# mugsyBrainBoard_p08.net
KiCad netlist of a schematic drawn in EAGLE
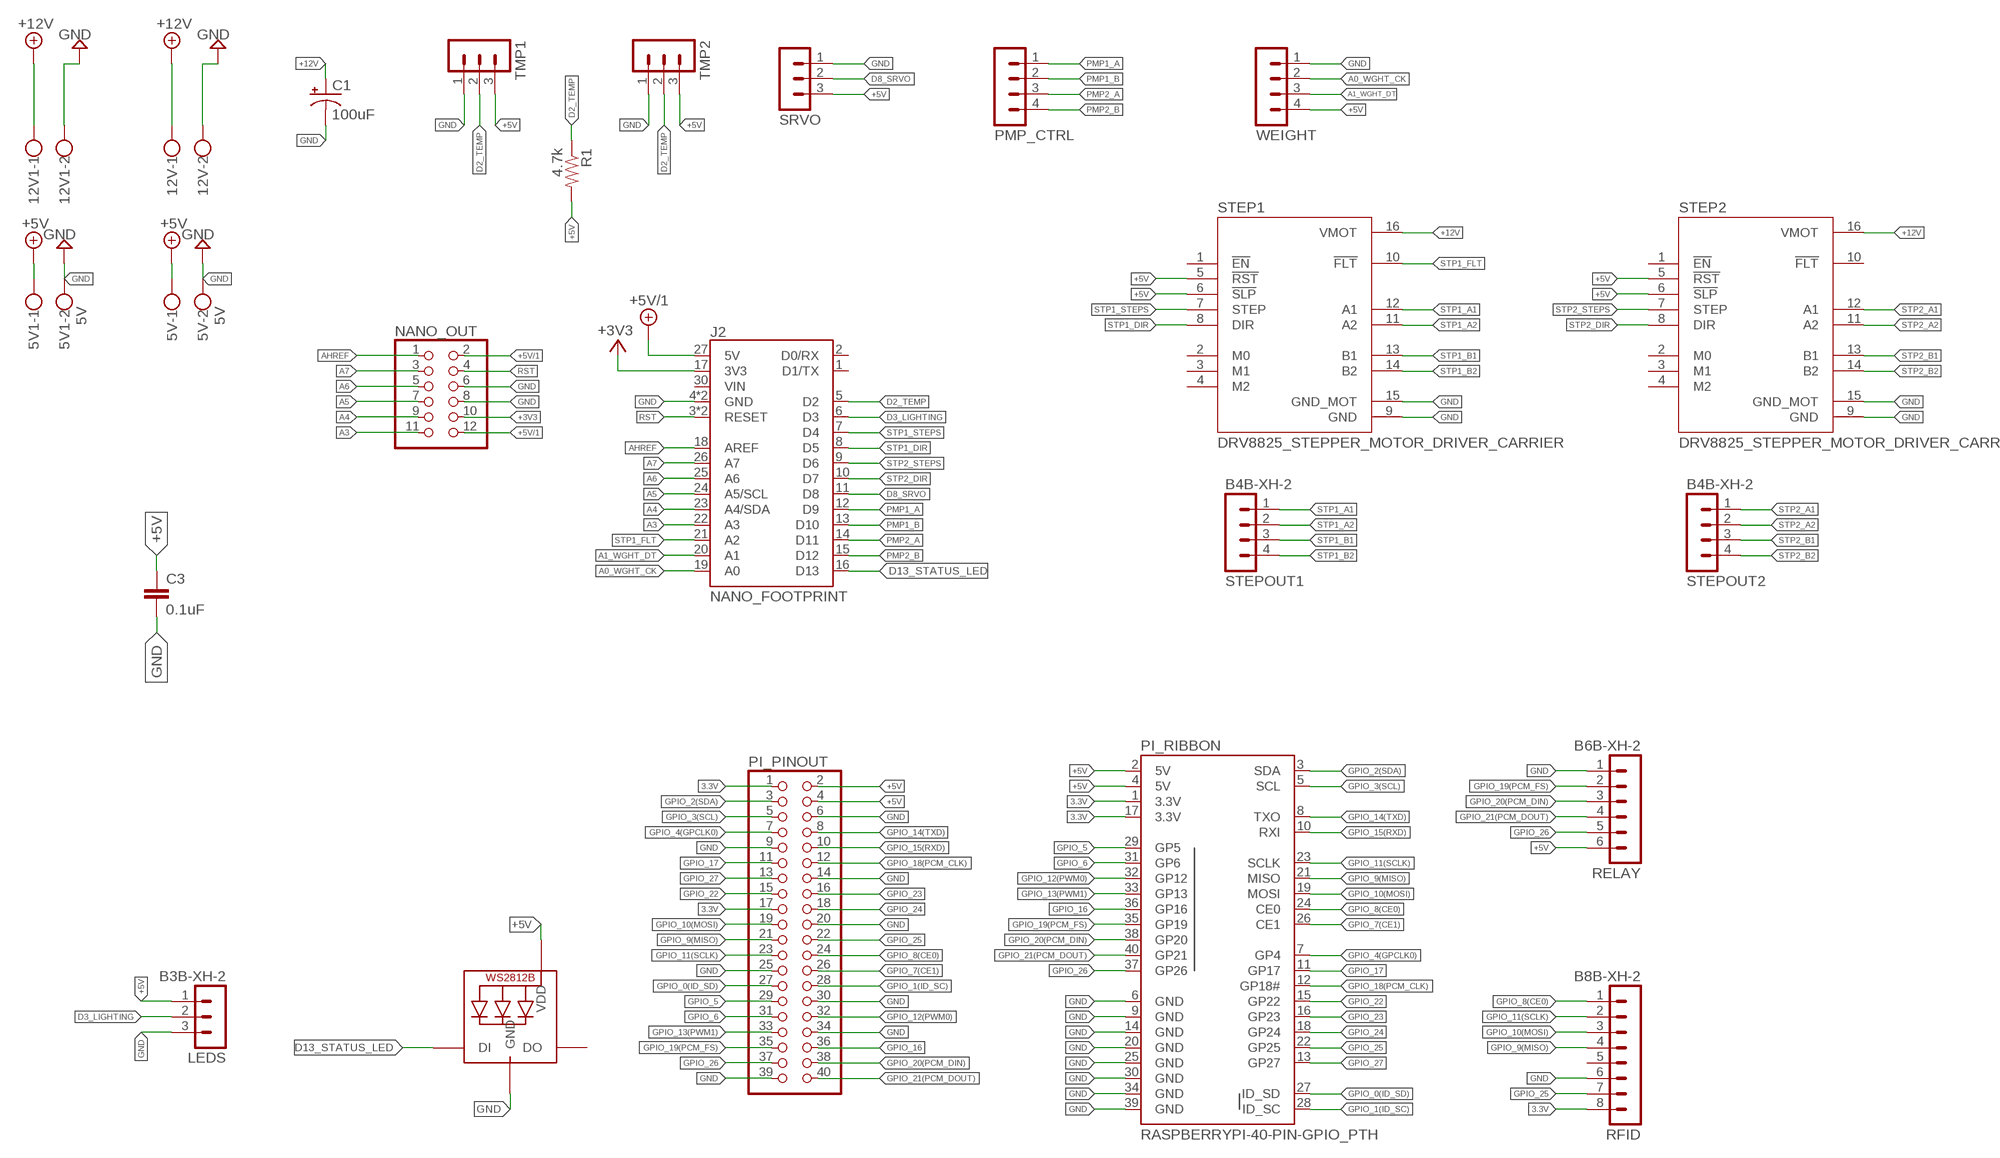
[diagram p0: schematic, sheet 1]

(export (version "E")
  (design (tool "Eeschema 10.0.6"))
  (components
    (comp (ref "5V")
      (value "5V")
      (footprint "eagle-import:W237-102")
      (fields (field (name "MPN") "237-102"))
      (libsource (lib "eagle-import") (part "W237-102"))
    )
    (comp (ref "5V1")
      (value "5V")
      (footprint "eagle-import:W237-102")
      (fields (field (name "MPN") "237-102"))
      (libsource (lib "eagle-import") (part "W237-102"))
    )
    (comp (ref "12V")
      (value "W237-102")
      (footprint "eagle-import:W237-102")
      (fields (field (name "MPN") "237-102"))
      (libsource (lib "eagle-import") (part "W237-102"))
    )
    (comp (ref "12V1")
      (value "W237-102")
      (footprint "eagle-import:W237-102")
      (fields (field (name "MPN") "237-102"))
      (libsource (lib "eagle-import") (part "W237-102"))
    )
    (comp (ref "C1")
      (value "100uF")
      (footprint "eagle-import:CPOL-RADIAL-2.5MM-6.5MM")
      (libsource (lib "eagle-import") (part "100UF-POLAR-RADIAL-2.5MM-25V-20%"))
    )
    (comp (ref "C3")
      (value "0.1uF")
      (footprint "eagle-import:C050-030X075")
      (libsource (lib "eagle-import") (part "C-EU050-030X075"))
    )
    (comp (ref "J2")
      (value "NANO_FOOTPRINT")
      (footprint "eagle-import:NANO")
      (libsource (lib "eagle-import") (part "NANO_FOOTPRINT"))
    )
    (comp (ref "LEDS")
      (value "B3B-XH-2")
      (footprint "eagle-import:B3B-XH-A")
      (libsource (lib "eagle-import") (part "B3B-XH-2"))
    )
    (comp (ref "NANO_OUT")
      (value "PINHD-2X6")
      (footprint "eagle-import:2X06")
      (libsource (lib "eagle-import") (part "PINHD-2X6"))
    )
    (comp (ref "PI_PINOUT")
      (value "PINHD-2X20")
      (footprint "eagle-import:2X20")
      (libsource (lib "eagle-import") (part "PINHD-2X20"))
    )
    (comp (ref "PI_RIBBON")
      (value "RASPBERRYPI-40-PIN-GPIO_PTH")
      (footprint "eagle-import:2X20_SHROUDED")
      (libsource (lib "eagle-import") (part "RASPBERRYPI-40-PIN-GPIO_PTH"))
    )
    (comp (ref "PMP_CTRL")
      (value "B4B-XH-2")
      (footprint "eagle-import:B4B-XH-A")
      (libsource (lib "eagle-import") (part "B4B-XH-2"))
    )
    (comp (ref "R1")
      (value "4.7k")
      (footprint "eagle-import:0207_5V")
      (libsource (lib "eagle-import") (part "R-US_0207/5V"))
    )
    (comp (ref "RELAY")
      (value "B6B-XH-2")
      (footprint "eagle-import:B6B-XH-A")
      (libsource (lib "eagle-import") (part "B6B-XH-2"))
    )
    (comp (ref "RFID")
      (value "B8B-XH-2")
      (footprint "eagle-import:B8B-XH-A")
      (libsource (lib "eagle-import") (part "B8B-XH-2"))
    )
    (comp (ref "SRVO")
      (value "B3B-XH-2")
      (footprint "eagle-import:B3B-XH-A")
      (libsource (lib "eagle-import") (part "B3B-XH-2"))
    )
    (comp (ref "STATUS")
      (value "WS2812B5050")
      (footprint "eagle-import:WS2812B")
      (libsource (lib "eagle-import") (part "WS2812B5050"))
    )
    (comp (ref "STEP1")
      (value "DRV8825_STEPPER_MOTOR_DRIVER_CARRIER")
      (footprint "eagle-import:IC_DRV8825_STEPPER_MOTOR_DRIVER_CARRIER")
      (fields (field (name "MF") "Pololu") (field (name "MP") "DRV8825 STEPPER MOTOR DRIVER CARRIER"))
      (libsource (lib "eagle-import") (part "DRV8825_STEPPER_MOTOR_DRIVER_CARRIER"))
    )
    (comp (ref "STEP2")
      (value "DRV8825_STEPPER_MOTOR_DRIVER_CARRIER")
      (footprint "eagle-import:IC_DRV8825_STEPPER_MOTOR_DRIVER_CARRIER")
      (fields (field (name "MF") "Pololu") (field (name "MP") "DRV8825 STEPPER MOTOR DRIVER CARRIER"))
      (libsource (lib "eagle-import") (part "DRV8825_STEPPER_MOTOR_DRIVER_CARRIER"))
    )
    (comp (ref "STEPOUT1")
      (value "B4B-XH-2")
      (footprint "eagle-import:B4B-XH-A")
      (libsource (lib "eagle-import") (part "B4B-XH-2"))
    )
    (comp (ref "STEPOUT2")
      (value "B4B-XH-2")
      (footprint "eagle-import:B4B-XH-A")
      (libsource (lib "eagle-import") (part "B4B-XH-2"))
    )
    (comp (ref "TMP1")
      (value "B3B-XH-2")
      (footprint "eagle-import:B3B-XH-A")
      (libsource (lib "eagle-import") (part "B3B-XH-2"))
    )
    (comp (ref "TMP2")
      (value "B3B-XH-2")
      (footprint "eagle-import:B3B-XH-A")
      (libsource (lib "eagle-import") (part "B3B-XH-2"))
    )
    (comp (ref "WEIGHT")
      (value "B4B-XH-2")
      (footprint "eagle-import:B4B-XH-A")
      (libsource (lib "eagle-import") (part "B4B-XH-2"))
    )
  )
  (nets
    (net (code "1") (name "+3V3") (class "Default")
      (node (ref "J2") (pin "17") (pinfunction "3V3_17") (pintype "bidirectional"))
      (node (ref "NANO_OUT") (pin "10") (pinfunction "10_10") (pintype "passive"))
    )
    (net (code "2") (name "+5V") (class "Default")
      (node (ref "5V") (pin "1") (pinfunction "KL_1") (pintype "passive"))
      (node (ref "5V1") (pin "1") (pinfunction "KL_1") (pintype "passive"))
      (node (ref "C3") (pin "1") (pinfunction "1_1") (pintype "passive"))
      (node (ref "LEDS") (pin "1") (pinfunction "1_1") (pintype "passive"))
      (node (ref "PI_PINOUT") (pin "2") (pinfunction "2_2") (pintype "passive"))
      (node (ref "PI_PINOUT") (pin "4") (pinfunction "4_4") (pintype "passive"))
      (node (ref "PI_RIBBON") (pin "2") (pinfunction "5V_2") (pintype "power_in"))
      (node (ref "PI_RIBBON") (pin "4") (pinfunction "5V_4") (pintype "power_in"))
      (node (ref "R1") (pin "2") (pinfunction "2_2") (pintype "passive"))
      (node (ref "RELAY") (pin "6") (pinfunction "6_6") (pintype "passive"))
      (node (ref "SRVO") (pin "3") (pinfunction "3_3") (pintype "passive"))
      (node (ref "STATUS") (pin "1-VDD") (pinfunction "VDD_1-VDD") (pintype "power_in"))
      (node (ref "STEP1") (pin "5") (pinfunction "~{RST}_5") (pintype "input"))
      (node (ref "STEP1") (pin "6") (pinfunction "~{SLP}_6") (pintype "input"))
      (node (ref "STEP2") (pin "5") (pinfunction "~{RST}_5") (pintype "input"))
      (node (ref "STEP2") (pin "6") (pinfunction "~{SLP}_6") (pintype "input"))
      (node (ref "TMP1") (pin "3") (pinfunction "3_3") (pintype "passive"))
      (node (ref "TMP2") (pin "3") (pinfunction "3_3") (pintype "passive"))
      (node (ref "WEIGHT") (pin "4") (pinfunction "4_4") (pintype "passive"))
    )
    (net (code "3") (name "+5V{slash}1") (class "Default")
      (node (ref "J2") (pin "27") (pinfunction "5V_27") (pintype "bidirectional"))
      (node (ref "NANO_OUT") (pin "12") (pinfunction "12_12") (pintype "passive"))
      (node (ref "NANO_OUT") (pin "2") (pinfunction "2_2") (pintype "passive"))
    )
    (net (code "4") (name "+12V") (class "Default")
      (node (ref "12V") (pin "1") (pinfunction "KL_1") (pintype "passive"))
      (node (ref "12V1") (pin "1") (pinfunction "KL_1") (pintype "passive"))
      (node (ref "C1") (pin "1") (pinfunction "+_1") (pintype "passive"))
      (node (ref "STEP1") (pin "16") (pinfunction "VMOT_16") (pintype "power_in"))
      (node (ref "STEP2") (pin "16") (pinfunction "VMOT_16") (pintype "power_in"))
    )
    (net (code "5") (name "3.3V") (class "Default")
      (node (ref "PI_PINOUT") (pin "1") (pinfunction "1_1") (pintype "passive"))
      (node (ref "PI_PINOUT") (pin "17") (pinfunction "17_17") (pintype "passive"))
      (node (ref "PI_RIBBON") (pin "1") (pinfunction "3.3V_1") (pintype "power_in"))
      (node (ref "PI_RIBBON") (pin "17") (pinfunction "3.3V_17") (pintype "power_in"))
      (node (ref "RFID") (pin "8") (pinfunction "8_8") (pintype "passive"))
    )
    (net (code "6") (name "A0_WGHT_CK") (class "Default")
      (node (ref "J2") (pin "19") (pinfunction "A0_19") (pintype "bidirectional"))
      (node (ref "WEIGHT") (pin "2") (pinfunction "2_2") (pintype "passive"))
    )
    (net (code "7") (name "A1_WGHT_DT") (class "Default")
      (node (ref "J2") (pin "20") (pinfunction "A1_20") (pintype "bidirectional"))
      (node (ref "WEIGHT") (pin "3") (pinfunction "3_3") (pintype "passive"))
    )
    (net (code "8") (name "A3") (class "Default")
      (node (ref "J2") (pin "22") (pinfunction "A3_22") (pintype "bidirectional"))
      (node (ref "NANO_OUT") (pin "11") (pinfunction "11_11") (pintype "passive"))
    )
    (net (code "9") (name "A4") (class "Default")
      (node (ref "J2") (pin "23") (pinfunction "A4/SDA_23") (pintype "bidirectional"))
      (node (ref "NANO_OUT") (pin "9") (pinfunction "9_9") (pintype "passive"))
    )
    (net (code "10") (name "A5") (class "Default")
      (node (ref "J2") (pin "24") (pinfunction "A5/SCL_24") (pintype "bidirectional"))
      (node (ref "NANO_OUT") (pin "7") (pinfunction "7_7") (pintype "passive"))
    )
    (net (code "11") (name "A6") (class "Default")
      (node (ref "J2") (pin "25") (pinfunction "A6_25") (pintype "bidirectional"))
      (node (ref "NANO_OUT") (pin "5") (pinfunction "5_5") (pintype "passive"))
    )
    (net (code "12") (name "A7") (class "Default")
      (node (ref "J2") (pin "26") (pinfunction "A7_26") (pintype "bidirectional"))
      (node (ref "NANO_OUT") (pin "3") (pinfunction "3_3") (pintype "passive"))
    )
    (net (code "13") (name "AHREF") (class "Default")
      (node (ref "J2") (pin "18") (pinfunction "AREF_18") (pintype "bidirectional"))
      (node (ref "NANO_OUT") (pin "1") (pinfunction "1_1") (pintype "passive"))
    )
    (net (code "14") (name "D2_TEMP") (class "Default")
      (node (ref "J2") (pin "5") (pinfunction "D2_5") (pintype "bidirectional"))
      (node (ref "R1") (pin "1") (pinfunction "1_1") (pintype "passive"))
      (node (ref "TMP1") (pin "2") (pinfunction "2_2") (pintype "passive"))
      (node (ref "TMP2") (pin "2") (pinfunction "2_2") (pintype "passive"))
    )
    (net (code "15") (name "D3_LIGHTING") (class "Default")
      (node (ref "J2") (pin "6") (pinfunction "D3_6") (pintype "bidirectional"))
      (node (ref "LEDS") (pin "2") (pinfunction "2_2") (pintype "passive"))
    )
    (net (code "16") (name "D8_SRVO") (class "Default")
      (node (ref "J2") (pin "11") (pinfunction "D8_11") (pintype "bidirectional"))
      (node (ref "SRVO") (pin "2") (pinfunction "2_2") (pintype "passive"))
    )
    (net (code "17") (name "D13_STATUS_LED") (class "Default")
      (node (ref "J2") (pin "16") (pinfunction "D13_16") (pintype "bidirectional"))
      (node (ref "STATUS") (pin "4-DIN") (pinfunction "DI_4-DIN") (pintype "input"))
    )
    (net (code "18") (name "GND") (class "Default")
      (node (ref "12V") (pin "2") (pinfunction "KL_2") (pintype "passive"))
      (node (ref "12V1") (pin "2") (pinfunction "KL_2") (pintype "passive"))
      (node (ref "5V") (pin "2") (pinfunction "KL_2") (pintype "passive"))
      (node (ref "5V1") (pin "2") (pinfunction "KL_2") (pintype "passive"))
      (node (ref "C1") (pin "2") (pinfunction "-_2") (pintype "passive"))
      (node (ref "C3") (pin "2") (pinfunction "2_2") (pintype "passive"))
      (node (ref "J2") (pin "29") (pinfunction "GND_29") (pintype "bidirectional"))
      (node (ref "J2") (pin "4") (pinfunction "GND_4") (pintype "bidirectional"))
      (node (ref "LEDS") (pin "3") (pinfunction "3_3") (pintype "passive"))
      (node (ref "NANO_OUT") (pin "6") (pinfunction "6_6") (pintype "passive"))
      (node (ref "NANO_OUT") (pin "8") (pinfunction "8_8") (pintype "passive"))
      (node (ref "PI_PINOUT") (pin "14") (pinfunction "14_14") (pintype "passive"))
      (node (ref "PI_PINOUT") (pin "20") (pinfunction "20_20") (pintype "passive"))
      (node (ref "PI_PINOUT") (pin "25") (pinfunction "25_25") (pintype "passive"))
      (node (ref "PI_PINOUT") (pin "30") (pinfunction "30_30") (pintype "passive"))
      (node (ref "PI_PINOUT") (pin "34") (pinfunction "34_34") (pintype "passive"))
      (node (ref "PI_PINOUT") (pin "39") (pinfunction "39_39") (pintype "passive"))
      (node (ref "PI_PINOUT") (pin "6") (pinfunction "6_6") (pintype "passive"))
      (node (ref "PI_PINOUT") (pin "9") (pinfunction "9_9") (pintype "passive"))
      (node (ref "PI_RIBBON") (pin "14") (pinfunction "GND_14") (pintype "power_in"))
      (node (ref "PI_RIBBON") (pin "20") (pinfunction "GND_20") (pintype "power_in"))
      (node (ref "PI_RIBBON") (pin "25") (pinfunction "GND_25") (pintype "power_in"))
      (node (ref "PI_RIBBON") (pin "30") (pinfunction "GND_30") (pintype "power_in"))
      (node (ref "PI_RIBBON") (pin "34") (pinfunction "GND_34") (pintype "power_in"))
      (node (ref "PI_RIBBON") (pin "39") (pinfunction "GND_39") (pintype "power_in"))
      (node (ref "PI_RIBBON") (pin "6") (pinfunction "GND_6") (pintype "power_in"))
      (node (ref "PI_RIBBON") (pin "9") (pinfunction "GND_9") (pintype "power_in"))
      (node (ref "RELAY") (pin "1") (pinfunction "1_1") (pintype "passive"))
      (node (ref "RFID") (pin "6") (pinfunction "6_6") (pintype "passive"))
      (node (ref "SRVO") (pin "1") (pinfunction "1_1") (pintype "passive"))
      (node (ref "STATUS") (pin "3-GND") (pinfunction "GND_3-GND") (pintype "power_in"))
      (node (ref "STEP1") (pin "15") (pinfunction "GND_MOT_15") (pintype "power_in"))
      (node (ref "STEP1") (pin "9") (pinfunction "GND_9") (pintype "power_in"))
      (node (ref "STEP2") (pin "15") (pinfunction "GND_MOT_15") (pintype "power_in"))
      (node (ref "STEP2") (pin "9") (pinfunction "GND_9") (pintype "power_in"))
      (node (ref "TMP1") (pin "1") (pinfunction "1_1") (pintype "passive"))
      (node (ref "TMP2") (pin "1") (pinfunction "1_1") (pintype "passive"))
      (node (ref "WEIGHT") (pin "1") (pinfunction "1_1") (pintype "passive"))
    )
    (net (code "19") (name "GPIO_0(ID_SD)") (class "Default")
      (node (ref "PI_PINOUT") (pin "27") (pinfunction "27_27") (pintype "passive"))
      (node (ref "PI_RIBBON") (pin "27") (pinfunction "ID_SD_27") (pintype "bidirectional"))
    )
    (net (code "20") (name "GPIO_1(ID_SC)") (class "Default")
      (node (ref "PI_PINOUT") (pin "28") (pinfunction "28_28") (pintype "passive"))
      (node (ref "PI_RIBBON") (pin "28") (pinfunction "ID_SC_28") (pintype "bidirectional"))
    )
    (net (code "21") (name "GPIO_2(SDA)") (class "Default")
      (node (ref "PI_PINOUT") (pin "3") (pinfunction "3_3") (pintype "passive"))
      (node (ref "PI_RIBBON") (pin "3") (pinfunction "SDA_3") (pintype "bidirectional"))
    )
    (net (code "22") (name "GPIO_3(SCL)") (class "Default")
      (node (ref "PI_PINOUT") (pin "5") (pinfunction "5_5") (pintype "passive"))
      (node (ref "PI_RIBBON") (pin "5") (pinfunction "SCL_5") (pintype "bidirectional"))
    )
    (net (code "23") (name "GPIO_4(GPCLK0)") (class "Default")
      (node (ref "PI_PINOUT") (pin "7") (pinfunction "7_7") (pintype "passive"))
      (node (ref "PI_RIBBON") (pin "7") (pinfunction "GP4_7") (pintype "bidirectional"))
    )
    (net (code "24") (name "GPIO_5") (class "Default")
      (node (ref "PI_PINOUT") (pin "29") (pinfunction "29_29") (pintype "passive"))
      (node (ref "PI_RIBBON") (pin "29") (pinfunction "GP5_29") (pintype "bidirectional"))
    )
    (net (code "25") (name "GPIO_6") (class "Default")
      (node (ref "PI_PINOUT") (pin "31") (pinfunction "31_31") (pintype "passive"))
      (node (ref "PI_RIBBON") (pin "31") (pinfunction "GP6_31") (pintype "bidirectional"))
    )
    (net (code "26") (name "GPIO_7(CE1)") (class "Default")
      (node (ref "PI_PINOUT") (pin "26") (pinfunction "26_26") (pintype "passive"))
      (node (ref "PI_RIBBON") (pin "26") (pinfunction "CE1_26") (pintype "output"))
    )
    (net (code "27") (name "GPIO_8(CE0)") (class "Default")
      (node (ref "PI_PINOUT") (pin "24") (pinfunction "24_24") (pintype "passive"))
      (node (ref "PI_RIBBON") (pin "24") (pinfunction "CE0_24") (pintype "output"))
      (node (ref "RFID") (pin "1") (pinfunction "1_1") (pintype "passive"))
    )
    (net (code "28") (name "GPIO_9(MISO)") (class "Default")
      (node (ref "PI_PINOUT") (pin "21") (pinfunction "21_21") (pintype "passive"))
      (node (ref "PI_RIBBON") (pin "21") (pinfunction "MISO_21") (pintype "input"))
      (node (ref "RFID") (pin "4") (pinfunction "4_4") (pintype "passive"))
    )
    (net (code "29") (name "GPIO_10(MOSI)") (class "Default")
      (node (ref "PI_PINOUT") (pin "19") (pinfunction "19_19") (pintype "passive"))
      (node (ref "PI_RIBBON") (pin "19") (pinfunction "MOSI_19") (pintype "output"))
      (node (ref "RFID") (pin "3") (pinfunction "3_3") (pintype "passive"))
    )
    (net (code "30") (name "GPIO_11(SCLK)") (class "Default")
      (node (ref "PI_PINOUT") (pin "23") (pinfunction "23_23") (pintype "passive"))
      (node (ref "PI_RIBBON") (pin "23") (pinfunction "SCLK_23") (pintype "output"))
      (node (ref "RFID") (pin "2") (pinfunction "2_2") (pintype "passive"))
    )
    (net (code "31") (name "GPIO_12(PWM0)") (class "Default")
      (node (ref "PI_PINOUT") (pin "32") (pinfunction "32_32") (pintype "passive"))
      (node (ref "PI_RIBBON") (pin "32") (pinfunction "GP12_32") (pintype "bidirectional"))
    )
    (net (code "32") (name "GPIO_13(PWM1)") (class "Default")
      (node (ref "PI_PINOUT") (pin "33") (pinfunction "33_33") (pintype "passive"))
      (node (ref "PI_RIBBON") (pin "33") (pinfunction "GP13_33") (pintype "bidirectional"))
    )
    (net (code "33") (name "GPIO_14(TXD)") (class "Default")
      (node (ref "PI_PINOUT") (pin "8") (pinfunction "8_8") (pintype "passive"))
      (node (ref "PI_RIBBON") (pin "8") (pinfunction "TXO_8") (pintype "output"))
    )
    (net (code "34") (name "GPIO_15(RXD)") (class "Default")
      (node (ref "PI_PINOUT") (pin "10") (pinfunction "10_10") (pintype "passive"))
      (node (ref "PI_RIBBON") (pin "10") (pinfunction "RXI_10") (pintype "input"))
    )
    (net (code "35") (name "GPIO_16") (class "Default")
      (node (ref "PI_PINOUT") (pin "36") (pinfunction "36_36") (pintype "passive"))
      (node (ref "PI_RIBBON") (pin "36") (pinfunction "GP16_36") (pintype "bidirectional"))
    )
    (net (code "36") (name "GPIO_17") (class "Default")
      (node (ref "PI_PINOUT") (pin "11") (pinfunction "11_11") (pintype "passive"))
      (node (ref "PI_RIBBON") (pin "11") (pinfunction "GP17_11") (pintype "bidirectional"))
    )
    (net (code "37") (name "GPIO_18(PCM_CLK)") (class "Default")
      (node (ref "PI_PINOUT") (pin "12") (pinfunction "12_12") (pintype "passive"))
      (node (ref "PI_RIBBON") (pin "12") (pinfunction "GP18#_12") (pintype "bidirectional"))
    )
    (net (code "38") (name "GPIO_19(PCM_FS)") (class "Default")
      (node (ref "PI_PINOUT") (pin "35") (pinfunction "35_35") (pintype "passive"))
      (node (ref "PI_RIBBON") (pin "35") (pinfunction "GP19_35") (pintype "bidirectional"))
      (node (ref "RELAY") (pin "2") (pinfunction "2_2") (pintype "passive"))
    )
    (net (code "39") (name "GPIO_20(PCM_DIN)") (class "Default")
      (node (ref "PI_PINOUT") (pin "38") (pinfunction "38_38") (pintype "passive"))
      (node (ref "PI_RIBBON") (pin "38") (pinfunction "GP20_38") (pintype "bidirectional"))
      (node (ref "RELAY") (pin "3") (pinfunction "3_3") (pintype "passive"))
    )
    (net (code "40") (name "GPIO_21(PCM_DOUT)") (class "Default")
      (node (ref "PI_PINOUT") (pin "40") (pinfunction "40_40") (pintype "passive"))
      (node (ref "PI_RIBBON") (pin "40") (pinfunction "GP21_40") (pintype "bidirectional"))
      (node (ref "RELAY") (pin "4") (pinfunction "4_4") (pintype "passive"))
    )
    (net (code "41") (name "GPIO_22") (class "Default")
      (node (ref "PI_PINOUT") (pin "15") (pinfunction "15_15") (pintype "passive"))
      (node (ref "PI_RIBBON") (pin "15") (pinfunction "GP22_15") (pintype "bidirectional"))
    )
    (net (code "42") (name "GPIO_23") (class "Default")
      (node (ref "PI_PINOUT") (pin "16") (pinfunction "16_16") (pintype "passive"))
      (node (ref "PI_RIBBON") (pin "16") (pinfunction "GP23_16") (pintype "bidirectional"))
    )
    (net (code "43") (name "GPIO_24") (class "Default")
      (node (ref "PI_PINOUT") (pin "18") (pinfunction "18_18") (pintype "passive"))
      (node (ref "PI_RIBBON") (pin "18") (pinfunction "GP24_18") (pintype "bidirectional"))
    )
    (net (code "44") (name "GPIO_25") (class "Default")
      (node (ref "PI_PINOUT") (pin "22") (pinfunction "22_22") (pintype "passive"))
      (node (ref "PI_RIBBON") (pin "22") (pinfunction "GP25_22") (pintype "bidirectional"))
      (node (ref "RFID") (pin "7") (pinfunction "7_7") (pintype "passive"))
    )
    (net (code "45") (name "GPIO_26") (class "Default")
      (node (ref "PI_PINOUT") (pin "37") (pinfunction "37_37") (pintype "passive"))
      (node (ref "PI_RIBBON") (pin "37") (pinfunction "GP26_37") (pintype "bidirectional"))
      (node (ref "RELAY") (pin "5") (pinfunction "5_5") (pintype "passive"))
    )
    (net (code "46") (name "GPIO_27") (class "Default")
      (node (ref "PI_PINOUT") (pin "13") (pinfunction "13_13") (pintype "passive"))
      (node (ref "PI_RIBBON") (pin "13") (pinfunction "GP27_13") (pintype "bidirectional"))
    )
    (net (code "47") (name "PMP1_A") (class "Default")
      (node (ref "J2") (pin "12") (pinfunction "D9_12") (pintype "bidirectional"))
      (node (ref "PMP_CTRL") (pin "1") (pinfunction "1_1") (pintype "passive"))
    )
    (net (code "48") (name "PMP1_B") (class "Default")
      (node (ref "J2") (pin "13") (pinfunction "D10_13") (pintype "bidirectional"))
      (node (ref "PMP_CTRL") (pin "2") (pinfunction "2_2") (pintype "passive"))
    )
    (net (code "49") (name "PMP2_A") (class "Default")
      (node (ref "J2") (pin "14") (pinfunction "D11_14") (pintype "bidirectional"))
      (node (ref "PMP_CTRL") (pin "3") (pinfunction "3_3") (pintype "passive"))
    )
    (net (code "50") (name "PMP2_B") (class "Default")
      (node (ref "J2") (pin "15") (pinfunction "D12_15") (pintype "bidirectional"))
      (node (ref "PMP_CTRL") (pin "4") (pinfunction "4_4") (pintype "passive"))
    )
    (net (code "51") (name "RST") (class "Default")
      (node (ref "J2") (pin "28") (pinfunction "RESET_28") (pintype "bidirectional"))
      (node (ref "J2") (pin "3") (pinfunction "RESET_3") (pintype "bidirectional"))
      (node (ref "NANO_OUT") (pin "4") (pinfunction "4_4") (pintype "passive"))
    )
    (net (code "52") (name "STP1_A1") (class "Default")
      (node (ref "STEP1") (pin "12") (pinfunction "A1_12") (pintype "output"))
      (node (ref "STEPOUT1") (pin "1") (pinfunction "1_1") (pintype "passive"))
    )
    (net (code "53") (name "STP1_A2") (class "Default")
      (node (ref "STEP1") (pin "11") (pinfunction "A2_11") (pintype "output"))
      (node (ref "STEPOUT1") (pin "2") (pinfunction "2_2") (pintype "passive"))
    )
    (net (code "54") (name "STP1_B1") (class "Default")
      (node (ref "STEP1") (pin "13") (pinfunction "B1_13") (pintype "output"))
      (node (ref "STEPOUT1") (pin "3") (pinfunction "3_3") (pintype "passive"))
    )
    (net (code "55") (name "STP1_B2") (class "Default")
      (node (ref "STEP1") (pin "14") (pinfunction "B2_14") (pintype "output"))
      (node (ref "STEPOUT1") (pin "4") (pinfunction "4_4") (pintype "passive"))
    )
    (net (code "56") (name "STP1_DIR") (class "Default")
      (node (ref "J2") (pin "8") (pinfunction "D5_8") (pintype "bidirectional"))
      (node (ref "STEP1") (pin "8") (pinfunction "DIR_8") (pintype "input"))
    )
    (net (code "57") (name "STP1_FLT") (class "Default")
      (node (ref "J2") (pin "21") (pinfunction "A2_21") (pintype "bidirectional"))
      (node (ref "STEP1") (pin "10") (pinfunction "~{FLT}_10") (pintype "output"))
    )
    (net (code "58") (name "STP1_STEPS") (class "Default")
      (node (ref "J2") (pin "7") (pinfunction "D4_7") (pintype "bidirectional"))
      (node (ref "STEP1") (pin "7") (pinfunction "STEP_7") (pintype "input"))
    )
    (net (code "59") (name "STP2_A1") (class "Default")
      (node (ref "STEP2") (pin "12") (pinfunction "A1_12") (pintype "output"))
      (node (ref "STEPOUT2") (pin "1") (pinfunction "1_1") (pintype "passive"))
    )
    (net (code "60") (name "STP2_A2") (class "Default")
      (node (ref "STEP2") (pin "11") (pinfunction "A2_11") (pintype "output"))
      (node (ref "STEPOUT2") (pin "2") (pinfunction "2_2") (pintype "passive"))
    )
    (net (code "61") (name "STP2_B1") (class "Default")
      (node (ref "STEP2") (pin "13") (pinfunction "B1_13") (pintype "output"))
      (node (ref "STEPOUT2") (pin "3") (pinfunction "3_3") (pintype "passive"))
    )
    (net (code "62") (name "STP2_B2") (class "Default")
      (node (ref "STEP2") (pin "14") (pinfunction "B2_14") (pintype "output"))
      (node (ref "STEPOUT2") (pin "4") (pinfunction "4_4") (pintype "passive"))
    )
    (net (code "63") (name "STP2_DIR") (class "Default")
      (node (ref "J2") (pin "10") (pinfunction "D7_10") (pintype "bidirectional"))
      (node (ref "STEP2") (pin "8") (pinfunction "DIR_8") (pintype "input"))
    )
    (net (code "64") (name "STP2_STEPS") (class "Default")
      (node (ref "J2") (pin "9") (pinfunction "D6_9") (pintype "bidirectional"))
      (node (ref "STEP2") (pin "7") (pinfunction "STEP_7") (pintype "input"))
    )
    (net (code "65") (name "unconnected-(J2-D0{slash}RX-Pad2)") (class "Default")
      (node (ref "J2") (pin "2") (pinfunction "D0/RX_2") (pintype "bidirectional"))
    )
    (net (code "66") (name "unconnected-(J2-D1{slash}TX-Pad1)") (class "Default")
      (node (ref "J2") (pin "1") (pinfunction "D1/TX_1") (pintype "bidirectional"))
    )
    (net (code "67") (name "unconnected-(J2-VIN-Pad30)") (class "Default")
      (node (ref "J2") (pin "30") (pinfunction "VIN_30") (pintype "bidirectional"))
    )
    (net (code "68") (name "unconnected-(RFID-Pad5)") (class "Default")
      (node (ref "RFID") (pin "5") (pinfunction "5_5") (pintype "passive"))
    )
    (net (code "69") (name "unconnected-(STATUS-DO-Pad2-DOUT)") (class "Default")
      (node (ref "STATUS") (pin "2-DOUT") (pinfunction "DO_2-DOUT") (pintype "output"))
    )
    (net (code "70") (name "unconnected-(STEP1-M0-Pad2)") (class "Default")
      (node (ref "STEP1") (pin "2") (pinfunction "M0_2") (pintype "input"))
    )
    (net (code "71") (name "unconnected-(STEP1-M1-Pad3)") (class "Default")
      (node (ref "STEP1") (pin "3") (pinfunction "M1_3") (pintype "input"))
    )
    (net (code "72") (name "unconnected-(STEP1-M2-Pad4)") (class "Default")
      (node (ref "STEP1") (pin "4") (pinfunction "M2_4") (pintype "input"))
    )
    (net (code "73") (name "unconnected-(STEP1-~{EN}-Pad1)") (class "Default")
      (node (ref "STEP1") (pin "1") (pinfunction "~{EN}_1") (pintype "input"))
    )
    (net (code "74") (name "unconnected-(STEP2-M0-Pad2)") (class "Default")
      (node (ref "STEP2") (pin "2") (pinfunction "M0_2") (pintype "input"))
    )
    (net (code "75") (name "unconnected-(STEP2-M1-Pad3)") (class "Default")
      (node (ref "STEP2") (pin "3") (pinfunction "M1_3") (pintype "input"))
    )
    (net (code "76") (name "unconnected-(STEP2-M2-Pad4)") (class "Default")
      (node (ref "STEP2") (pin "4") (pinfunction "M2_4") (pintype "input"))
    )
    (net (code "77") (name "unconnected-(STEP2-~{EN}-Pad1)") (class "Default")
      (node (ref "STEP2") (pin "1") (pinfunction "~{EN}_1") (pintype "input"))
    )
    (net (code "78") (name "unconnected-(STEP2-~{FLT}-Pad10)") (class "Default")
      (node (ref "STEP2") (pin "10") (pinfunction "~{FLT}_10") (pintype "output"))
    )
  )
)
